# POWER.net
KiCad netlist of a schematic drawn in Altium Designer
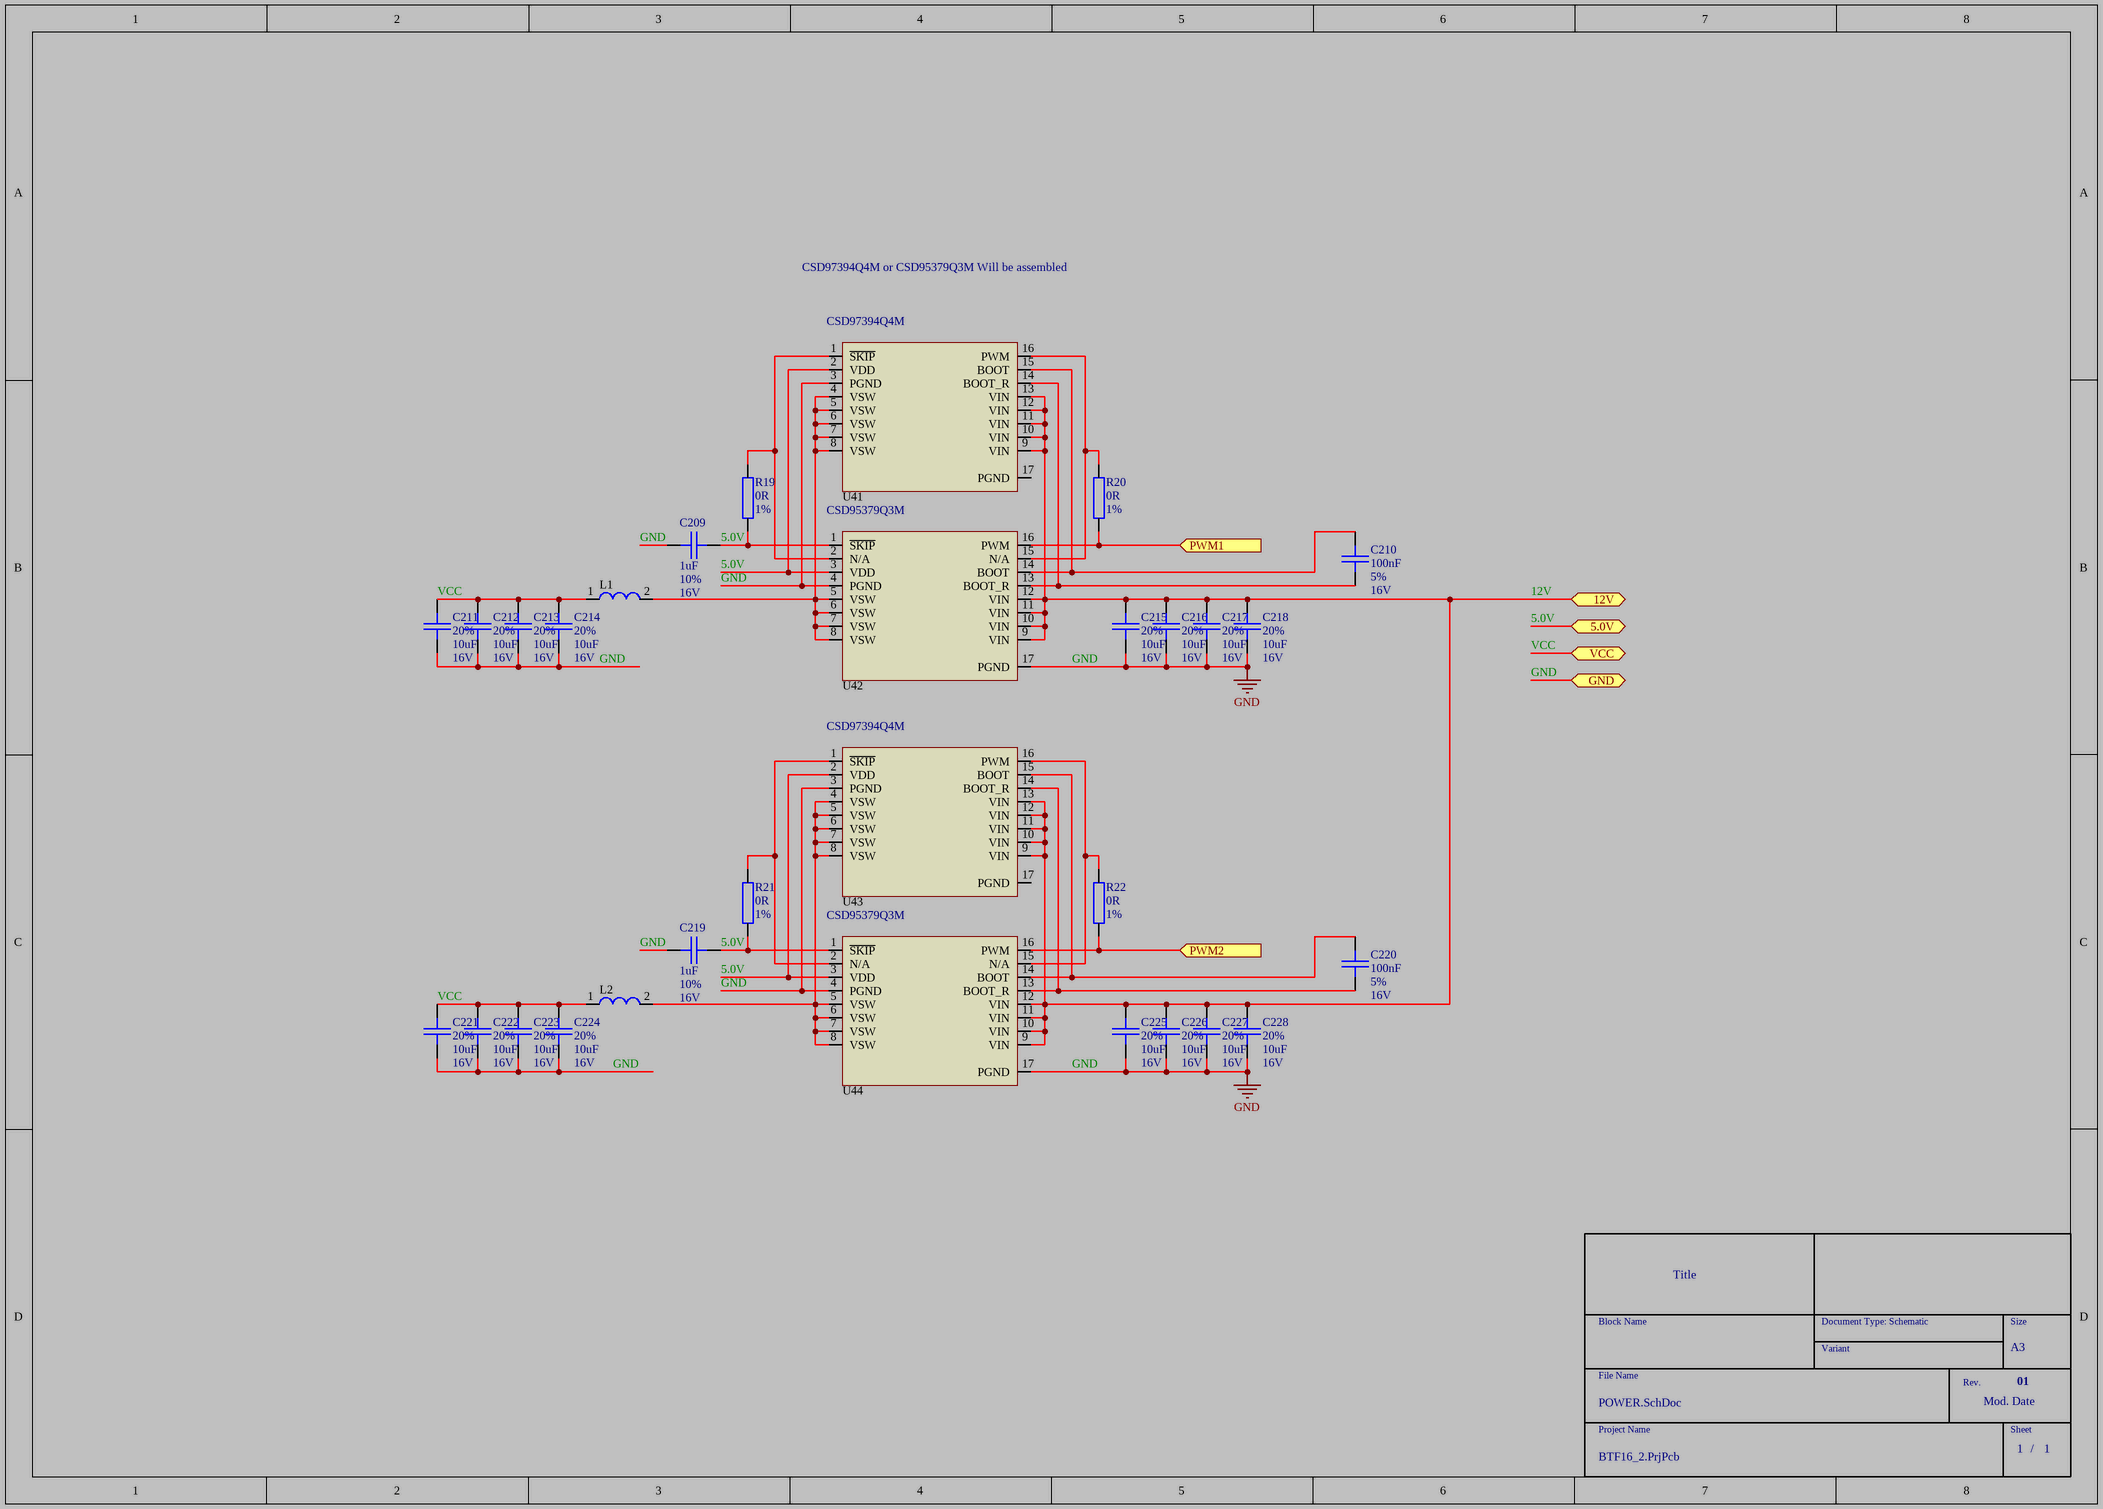
[diagram p0: POWER.SchDoc]

(export (version "E")
  (design (tool "Eeschema 10.0.6"))
  (components
    (comp (ref "C209")
      (value "C")
      (footprint "SMD_0603_CAPC1608X95N")
      (fields
        (field (name "DB_PART_NUMBER") "CAP000023307")
        (field (name "DB_VALUE") "1uF")
        (field (name "DB_TOLERANCE") "10%")
        (field (name "DB_VOLTAGE") "16V")
        (field (name "DB_MANUFACTURER_PART") "KEMET    C0603F105K4RAC")
      )
      (libsource (lib "Database_Libs1") (part "C"))
    )
    (comp (ref "C210")
      (value "C")
      (footprint "SMD_0603_CAPC1608X95N")
      (fields
        (field (name "DB_PART_NUMBER") "CAP000027134")
        (field (name "DB_VALUE") "100nF")
        (field (name "DB_TOLERANCE") "5%")
        (field (name "DB_VOLTAGE") "16V")
        (field (name "DB_MANUFACTURER_PART") "KEMET    C0603C104J4RAC")
      )
      (libsource (lib "Database_Libs1") (part "C"))
    )
    (comp (ref "C211")
      (value "C")
      (footprint "SMD_0805_CAPC2012X145N")
      (fields
        (field (name "DB_MANUFACTURER_PART") "KEMET    C0805C106M4PAC")
        (field (name "DB_PART_NUMBER") "CAP000043650")
        (field (name "DB_TOLERANCE") "20%")
        (field (name "DB_VALUE") "10uF")
        (field (name "DB_VOLTAGE") "16V")
      )
      (libsource (lib "Database_Libs1") (part "C"))
    )
    (comp (ref "C212")
      (value "C")
      (footprint "SMD_0805_CAPC2012X145N")
      (fields
        (field (name "DB_MANUFACTURER_PART") "KEMET    C0805C106M4PAC")
        (field (name "DB_PART_NUMBER") "CAP000043650")
        (field (name "DB_TOLERANCE") "20%")
        (field (name "DB_VALUE") "10uF")
        (field (name "DB_VOLTAGE") "16V")
      )
      (libsource (lib "Database_Libs1") (part "C"))
    )
    (comp (ref "C213")
      (value "C")
      (footprint "SMD_0805_CAPC2012X145N")
      (fields
        (field (name "DB_MANUFACTURER_PART") "KEMET    C0805C106M4PAC")
        (field (name "DB_PART_NUMBER") "CAP000043650")
        (field (name "DB_TOLERANCE") "20%")
        (field (name "DB_VALUE") "10uF")
        (field (name "DB_VOLTAGE") "16V")
      )
      (libsource (lib "Database_Libs1") (part "C"))
    )
    (comp (ref "C214")
      (value "C")
      (footprint "SMD_0805_CAPC2012X145N")
      (fields
        (field (name "DB_MANUFACTURER_PART") "KEMET    C0805C106M4PAC")
        (field (name "DB_PART_NUMBER") "CAP000043650")
        (field (name "DB_TOLERANCE") "20%")
        (field (name "DB_VALUE") "10uF")
        (field (name "DB_VOLTAGE") "16V")
      )
      (libsource (lib "Database_Libs1") (part "C"))
    )
    (comp (ref "C215")
      (value "C")
      (footprint "SMD_0805_CAPC2012X145N")
      (fields
        (field (name "DB_MANUFACTURER_PART") "KEMET    C0805C106M4PAC")
        (field (name "DB_PART_NUMBER") "CAP000043650")
        (field (name "DB_TOLERANCE") "20%")
        (field (name "DB_VALUE") "10uF")
        (field (name "DB_VOLTAGE") "16V")
      )
      (libsource (lib "Database_Libs1") (part "C"))
    )
    (comp (ref "C216")
      (value "C")
      (footprint "SMD_0805_CAPC2012X145N")
      (fields
        (field (name "DB_MANUFACTURER_PART") "KEMET    C0805C106M4PAC")
        (field (name "DB_PART_NUMBER") "CAP000043650")
        (field (name "DB_TOLERANCE") "20%")
        (field (name "DB_VALUE") "10uF")
        (field (name "DB_VOLTAGE") "16V")
      )
      (libsource (lib "Database_Libs1") (part "C"))
    )
    (comp (ref "C217")
      (value "C")
      (footprint "SMD_0805_CAPC2012X145N")
      (fields
        (field (name "DB_MANUFACTURER_PART") "KEMET    C0805C106M4PAC")
        (field (name "DB_PART_NUMBER") "CAP000043650")
        (field (name "DB_TOLERANCE") "20%")
        (field (name "DB_VALUE") "10uF")
        (field (name "DB_VOLTAGE") "16V")
      )
      (libsource (lib "Database_Libs1") (part "C"))
    )
    (comp (ref "C218")
      (value "C")
      (footprint "SMD_0805_CAPC2012X145N")
      (fields
        (field (name "DB_MANUFACTURER_PART") "KEMET    C0805C106M4PAC")
        (field (name "DB_PART_NUMBER") "CAP000043650")
        (field (name "DB_TOLERANCE") "20%")
        (field (name "DB_VALUE") "10uF")
        (field (name "DB_VOLTAGE") "16V")
      )
      (libsource (lib "Database_Libs1") (part "C"))
    )
    (comp (ref "C219")
      (value "C")
      (footprint "SMD_0603_CAPC1608X95N")
      (fields
        (field (name "DB_PART_NUMBER") "CAP000023307")
        (field (name "DB_VALUE") "1uF")
        (field (name "DB_TOLERANCE") "10%")
        (field (name "DB_VOLTAGE") "16V")
        (field (name "DB_MANUFACTURER_PART") "KEMET    C0603F105K4RAC")
      )
      (libsource (lib "Database_Libs1") (part "C"))
    )
    (comp (ref "C220")
      (value "C")
      (footprint "SMD_0603_CAPC1608X95N")
      (fields
        (field (name "DB_PART_NUMBER") "CAP000027134")
        (field (name "DB_VALUE") "100nF")
        (field (name "DB_TOLERANCE") "5%")
        (field (name "DB_VOLTAGE") "16V")
        (field (name "DB_MANUFACTURER_PART") "KEMET    C0603C104J4RAC")
      )
      (libsource (lib "Database_Libs1") (part "C"))
    )
    (comp (ref "C221")
      (value "C")
      (footprint "SMD_0805_CAPC2012X145N")
      (fields
        (field (name "DB_MANUFACTURER_PART") "KEMET    C0805C106M4PAC")
        (field (name "DB_PART_NUMBER") "CAP000043650")
        (field (name "DB_TOLERANCE") "20%")
        (field (name "DB_VALUE") "10uF")
        (field (name "DB_VOLTAGE") "16V")
      )
      (libsource (lib "Database_Libs1") (part "C"))
    )
    (comp (ref "C222")
      (value "C")
      (footprint "SMD_0805_CAPC2012X145N")
      (fields
        (field (name "DB_MANUFACTURER_PART") "KEMET    C0805C106M4PAC")
        (field (name "DB_PART_NUMBER") "CAP000043650")
        (field (name "DB_TOLERANCE") "20%")
        (field (name "DB_VALUE") "10uF")
        (field (name "DB_VOLTAGE") "16V")
      )
      (libsource (lib "Database_Libs1") (part "C"))
    )
    (comp (ref "C223")
      (value "C")
      (footprint "SMD_0805_CAPC2012X145N")
      (fields
        (field (name "DB_MANUFACTURER_PART") "KEMET    C0805C106M4PAC")
        (field (name "DB_PART_NUMBER") "CAP000043650")
        (field (name "DB_TOLERANCE") "20%")
        (field (name "DB_VALUE") "10uF")
        (field (name "DB_VOLTAGE") "16V")
      )
      (libsource (lib "Database_Libs1") (part "C"))
    )
    (comp (ref "C224")
      (value "C")
      (footprint "SMD_0805_CAPC2012X145N")
      (fields
        (field (name "DB_MANUFACTURER_PART") "KEMET    C0805C106M4PAC")
        (field (name "DB_PART_NUMBER") "CAP000043650")
        (field (name "DB_TOLERANCE") "20%")
        (field (name "DB_VALUE") "10uF")
        (field (name "DB_VOLTAGE") "16V")
      )
      (libsource (lib "Database_Libs1") (part "C"))
    )
    (comp (ref "C225")
      (value "C")
      (footprint "SMD_0805_CAPC2012X145N")
      (fields
        (field (name "DB_MANUFACTURER_PART") "KEMET    C0805C106M4PAC")
        (field (name "DB_PART_NUMBER") "CAP000043650")
        (field (name "DB_TOLERANCE") "20%")
        (field (name "DB_VALUE") "10uF")
        (field (name "DB_VOLTAGE") "16V")
      )
      (libsource (lib "Database_Libs1") (part "C"))
    )
    (comp (ref "C226")
      (value "C")
      (footprint "SMD_0805_CAPC2012X145N")
      (fields
        (field (name "DB_MANUFACTURER_PART") "KEMET    C0805C106M4PAC")
        (field (name "DB_PART_NUMBER") "CAP000043650")
        (field (name "DB_TOLERANCE") "20%")
        (field (name "DB_VALUE") "10uF")
        (field (name "DB_VOLTAGE") "16V")
      )
      (libsource (lib "Database_Libs1") (part "C"))
    )
    (comp (ref "C227")
      (value "C")
      (footprint "SMD_0805_CAPC2012X145N")
      (fields
        (field (name "DB_MANUFACTURER_PART") "KEMET    C0805C106M4PAC")
        (field (name "DB_PART_NUMBER") "CAP000043650")
        (field (name "DB_TOLERANCE") "20%")
        (field (name "DB_VALUE") "10uF")
        (field (name "DB_VOLTAGE") "16V")
      )
      (libsource (lib "Database_Libs1") (part "C"))
    )
    (comp (ref "C228")
      (value "C")
      (footprint "SMD_0805_CAPC2012X145N")
      (fields
        (field (name "DB_MANUFACTURER_PART") "KEMET    C0805C106M4PAC")
        (field (name "DB_PART_NUMBER") "CAP000043650")
        (field (name "DB_TOLERANCE") "20%")
        (field (name "DB_VALUE") "10uF")
        (field (name "DB_VOLTAGE") "16V")
      )
      (libsource (lib "Database_Libs1") (part "C"))
    )
    (comp (ref "L1") (value "470nH") (footprint "SMD_INDM720X665X300") (libsource (lib "DLV") (part "L")))
    (comp (ref "L2") (value "470nH") (footprint "SMD_INDM720X665X300") (libsource (lib "DLV") (part "L")))
    (comp (ref "R19")
      (value "R")
      (footprint "SMD_0603_RESC1608X55N")
      (fields
        (field (name "DB_PART_NUMBER") "RES000008926")
        (field (name "DB_VALUE") "0R")
        (field (name "DB_TOLERANCE") "1%")
        (field (name "DB_MANUFACTURER_PART") "YAGEO    AC0603FR-070RL")
        (field (name "DB_APPROVED_BY") "VSN")
      )
      (libsource (lib "Database_Libs1") (part "R"))
    )
    (comp (ref "R20")
      (value "R")
      (footprint "SMD_0603_RESC1608X55N")
      (fields
        (field (name "DB_PART_NUMBER") "RES000008926")
        (field (name "DB_VALUE") "0R")
        (field (name "DB_TOLERANCE") "1%")
        (field (name "DB_MANUFACTURER_PART") "YAGEO    AC0603FR-070RL")
        (field (name "DB_APPROVED_BY") "VSN")
      )
      (libsource (lib "Database_Libs1") (part "R"))
    )
    (comp (ref "R21")
      (value "R")
      (footprint "SMD_0603_RESC1608X55N")
      (fields
        (field (name "DB_PART_NUMBER") "RES000008926")
        (field (name "DB_VALUE") "0R")
        (field (name "DB_TOLERANCE") "1%")
        (field (name "DB_MANUFACTURER_PART") "YAGEO    AC0603FR-070RL")
        (field (name "DB_APPROVED_BY") "VSN")
      )
      (libsource (lib "Database_Libs1") (part "R"))
    )
    (comp (ref "R22")
      (value "R")
      (footprint "SMD_0603_RESC1608X55N")
      (fields
        (field (name "DB_PART_NUMBER") "RES000008926")
        (field (name "DB_VALUE") "0R")
        (field (name "DB_TOLERANCE") "1%")
        (field (name "DB_MANUFACTURER_PART") "YAGEO    AC0603FR-070RL")
        (field (name "DB_APPROVED_BY") "VSN")
      )
      (libsource (lib "Database_Libs1") (part "R"))
    )
    (comp (ref "U41")
      (value "CSD95379Q3M")
      (footprint "SMD_SON40P330X330X100-17N")
      (description "Texas Instrumendts Buck Boost DC-DC")
      (fields
        (field (name "DB_MANUFACTURER_PART") "TEXAS INSTRUMENTS  CSD97394Q4M")
        (field (name "DB_VALUE") "CSD97394Q4M")
      )
      (libsource (lib "BitCoin") (part "IC_CSD97394Q4M"))
    )
    (comp (ref "U42")
      (value "CSD95379Q3M")
      (footprint "SMD_SON40P330X330X100-17N")
      (description "Texas Instrumendts Buck Boost DC-DC")
      (fields
        (field (name "DB_MANUFACTURER_PART") "TEXAS INSTRUMENTS  CSD95379Q3M")
        (field (name "DB_VALUE") "CSD95379Q3M")
      )
      (libsource (lib "BitCoin") (part "IC_CSD95379Q3M"))
    )
    (comp (ref "U43")
      (value "CSD95379Q3M")
      (footprint "SMD_SON40P330X330X100-17N")
      (description "Texas Instrumendts Buck Boost DC-DC")
      (fields
        (field (name "DB_MANUFACTURER_PART") "TEXAS INSTRUMENTS  CSD97394Q4M")
        (field (name "DB_VALUE") "CSD97394Q4M")
      )
      (libsource (lib "BitCoin") (part "IC_CSD97394Q4M"))
    )
    (comp (ref "U44")
      (value "CSD95379Q3M")
      (footprint "SMD_SON40P330X330X100-17N")
      (description "Texas Instrumendts Buck Boost DC-DC")
      (fields
        (field (name "DB_MANUFACTURER_PART") "TEXAS INSTRUMENTS  CSD95379Q3M")
        (field (name "DB_VALUE") "CSD95379Q3M")
      )
      (libsource (lib "BitCoin") (part "IC_CSD95379Q3M"))
    )
  )
  (nets
    (net (code "1") (name "/5.0V") (class "Default")
      (node (ref "C209") (pin "1") (pinfunction "1_1") (pintype "passive"))
      (node (ref "C219") (pin "1") (pinfunction "1_1") (pintype "passive"))
      (node (ref "R19") (pin "1") (pinfunction "1_1") (pintype "passive"))
      (node (ref "R21") (pin "1") (pinfunction "1_1") (pintype "passive"))
      (node (ref "U41") (pin "2") (pinfunction "VDD_2") (pintype "passive"))
      (node (ref "U42") (pin "1") (pinfunction "~{SKIP}_1") (pintype "passive"))
      (node (ref "U42") (pin "3") (pinfunction "VDD_3") (pintype "passive"))
      (node (ref "U43") (pin "2") (pinfunction "VDD_2") (pintype "passive"))
      (node (ref "U44") (pin "1") (pinfunction "~{SKIP}_1") (pintype "passive"))
      (node (ref "U44") (pin "3") (pinfunction "VDD_3") (pintype "passive"))
    )
    (net (code "2") (name "/12V") (class "Default")
      (node (ref "C215") (pin "1") (pinfunction "1_1") (pintype "passive"))
      (node (ref "C216") (pin "1") (pinfunction "1_1") (pintype "passive"))
      (node (ref "C217") (pin "1") (pinfunction "1_1") (pintype "passive"))
      (node (ref "C218") (pin "1") (pinfunction "1_1") (pintype "passive"))
      (node (ref "C225") (pin "1") (pinfunction "1_1") (pintype "passive"))
      (node (ref "C226") (pin "1") (pinfunction "1_1") (pintype "passive"))
      (node (ref "C227") (pin "1") (pinfunction "1_1") (pintype "passive"))
      (node (ref "C228") (pin "1") (pinfunction "1_1") (pintype "passive"))
      (node (ref "U41") (pin "10") (pinfunction "VIN_10") (pintype "passive"))
      (node (ref "U41") (pin "11") (pinfunction "VIN_11") (pintype "passive"))
      (node (ref "U41") (pin "12") (pinfunction "VIN_12") (pintype "passive"))
      (node (ref "U41") (pin "13") (pinfunction "VIN_13") (pintype "passive"))
      (node (ref "U41") (pin "9") (pinfunction "VIN_9") (pintype "passive"))
      (node (ref "U42") (pin "10") (pinfunction "VIN_10") (pintype "passive"))
      (node (ref "U42") (pin "11") (pinfunction "VIN_11") (pintype "passive"))
      (node (ref "U42") (pin "12") (pinfunction "VIN_12") (pintype "passive"))
      (node (ref "U42") (pin "9") (pinfunction "VIN_9") (pintype "passive"))
      (node (ref "U43") (pin "10") (pinfunction "VIN_10") (pintype "passive"))
      (node (ref "U43") (pin "11") (pinfunction "VIN_11") (pintype "passive"))
      (node (ref "U43") (pin "12") (pinfunction "VIN_12") (pintype "passive"))
      (node (ref "U43") (pin "13") (pinfunction "VIN_13") (pintype "passive"))
      (node (ref "U43") (pin "9") (pinfunction "VIN_9") (pintype "passive"))
      (node (ref "U44") (pin "10") (pinfunction "VIN_10") (pintype "passive"))
      (node (ref "U44") (pin "11") (pinfunction "VIN_11") (pintype "passive"))
      (node (ref "U44") (pin "12") (pinfunction "VIN_12") (pintype "passive"))
      (node (ref "U44") (pin "9") (pinfunction "VIN_9") (pintype "passive"))
    )
    (net (code "3") (name "/PWM1") (class "Default")
      (node (ref "R20") (pin "1") (pinfunction "1_1") (pintype "passive"))
      (node (ref "U42") (pin "16") (pinfunction "PWM_16") (pintype "passive"))
    )
    (net (code "4") (name "/PWM2") (class "Default")
      (node (ref "R22") (pin "1") (pinfunction "1_1") (pintype "passive"))
      (node (ref "U44") (pin "16") (pinfunction "PWM_16") (pintype "passive"))
    )
    (net (code "5") (name "/VCC") (class "Default")
      (node (ref "C211") (pin "1") (pinfunction "1_1") (pintype "passive"))
      (node (ref "C212") (pin "1") (pinfunction "1_1") (pintype "passive"))
      (node (ref "C213") (pin "1") (pinfunction "1_1") (pintype "passive"))
      (node (ref "C214") (pin "1") (pinfunction "1_1") (pintype "passive"))
      (node (ref "C221") (pin "1") (pinfunction "1_1") (pintype "passive"))
      (node (ref "C222") (pin "1") (pinfunction "1_1") (pintype "passive"))
      (node (ref "C223") (pin "1") (pinfunction "1_1") (pintype "passive"))
      (node (ref "C224") (pin "1") (pinfunction "1_1") (pintype "passive"))
      (node (ref "L1") (pin "1") (pinfunction "1_1") (pintype "passive"))
      (node (ref "L2") (pin "1") (pinfunction "1_1") (pintype "passive"))
    )
    (net (code "6") (name "GND") (class "Default")
      (node (ref "C209") (pin "2") (pinfunction "2_2") (pintype "passive"))
      (node (ref "C211") (pin "2") (pinfunction "2_2") (pintype "passive"))
      (node (ref "C212") (pin "2") (pinfunction "2_2") (pintype "passive"))
      (node (ref "C213") (pin "2") (pinfunction "2_2") (pintype "passive"))
      (node (ref "C214") (pin "2") (pinfunction "2_2") (pintype "passive"))
      (node (ref "C215") (pin "2") (pinfunction "2_2") (pintype "passive"))
      (node (ref "C216") (pin "2") (pinfunction "2_2") (pintype "passive"))
      (node (ref "C217") (pin "2") (pinfunction "2_2") (pintype "passive"))
      (node (ref "C218") (pin "2") (pinfunction "2_2") (pintype "passive"))
      (node (ref "C219") (pin "2") (pinfunction "2_2") (pintype "passive"))
      (node (ref "C221") (pin "2") (pinfunction "2_2") (pintype "passive"))
      (node (ref "C222") (pin "2") (pinfunction "2_2") (pintype "passive"))
      (node (ref "C223") (pin "2") (pinfunction "2_2") (pintype "passive"))
      (node (ref "C224") (pin "2") (pinfunction "2_2") (pintype "passive"))
      (node (ref "C225") (pin "2") (pinfunction "2_2") (pintype "passive"))
      (node (ref "C226") (pin "2") (pinfunction "2_2") (pintype "passive"))
      (node (ref "C227") (pin "2") (pinfunction "2_2") (pintype "passive"))
      (node (ref "C228") (pin "2") (pinfunction "2_2") (pintype "passive"))
      (node (ref "U41") (pin "3") (pinfunction "PGND_3") (pintype "passive"))
      (node (ref "U42") (pin "17") (pinfunction "PGND_17") (pintype "passive"))
      (node (ref "U42") (pin "4") (pinfunction "PGND_4") (pintype "passive"))
      (node (ref "U43") (pin "3") (pinfunction "PGND_3") (pintype "passive"))
      (node (ref "U44") (pin "17") (pinfunction "PGND_17") (pintype "passive"))
      (node (ref "U44") (pin "4") (pinfunction "PGND_4") (pintype "passive"))
    )
    (net (code "7") (name "Net-(L1-Pad2)") (class "Default")
      (node (ref "L1") (pin "2") (pinfunction "2_2") (pintype "passive"))
      (node (ref "U41") (pin "4") (pinfunction "VSW_4") (pintype "passive"))
      (node (ref "U41") (pin "5") (pinfunction "VSW_5") (pintype "passive"))
      (node (ref "U41") (pin "6") (pinfunction "VSW_6") (pintype "passive"))
      (node (ref "U41") (pin "7") (pinfunction "VSW_7") (pintype "passive"))
      (node (ref "U41") (pin "8") (pinfunction "VSW_8") (pintype "passive"))
      (node (ref "U42") (pin "5") (pinfunction "VSW_5") (pintype "passive"))
      (node (ref "U42") (pin "6") (pinfunction "VSW_6") (pintype "passive"))
      (node (ref "U42") (pin "7") (pinfunction "VSW_7") (pintype "passive"))
      (node (ref "U42") (pin "8") (pinfunction "VSW_8") (pintype "passive"))
    )
    (net (code "8") (name "Net-(L2-Pad2)") (class "Default")
      (node (ref "L2") (pin "2") (pinfunction "2_2") (pintype "passive"))
      (node (ref "U43") (pin "4") (pinfunction "VSW_4") (pintype "passive"))
      (node (ref "U43") (pin "5") (pinfunction "VSW_5") (pintype "passive"))
      (node (ref "U43") (pin "6") (pinfunction "VSW_6") (pintype "passive"))
      (node (ref "U43") (pin "7") (pinfunction "VSW_7") (pintype "passive"))
      (node (ref "U43") (pin "8") (pinfunction "VSW_8") (pintype "passive"))
      (node (ref "U44") (pin "5") (pinfunction "VSW_5") (pintype "passive"))
      (node (ref "U44") (pin "6") (pinfunction "VSW_6") (pintype "passive"))
      (node (ref "U44") (pin "7") (pinfunction "VSW_7") (pintype "passive"))
      (node (ref "U44") (pin "8") (pinfunction "VSW_8") (pintype "passive"))
    )
    (net (code "9") (name "Net-(U41-BOOT)") (class "Default")
      (node (ref "C210") (pin "1") (pinfunction "1_1") (pintype "passive"))
      (node (ref "U41") (pin "15") (pinfunction "BOOT_15") (pintype "passive"))
      (node (ref "U42") (pin "14") (pinfunction "BOOT_14") (pintype "passive"))
    )
    (net (code "10") (name "Net-(U41-BOOT_R)") (class "Default")
      (node (ref "C210") (pin "2") (pinfunction "2_2") (pintype "passive"))
      (node (ref "U41") (pin "14") (pinfunction "BOOT_R_14") (pintype "passive"))
      (node (ref "U42") (pin "13") (pinfunction "BOOT_R_13") (pintype "passive"))
    )
    (net (code "11") (name "Net-(U41-PWM)") (class "Default")
      (node (ref "R20") (pin "2") (pinfunction "2_2") (pintype "passive"))
      (node (ref "U41") (pin "16") (pinfunction "PWM_16") (pintype "passive"))
      (node (ref "U42") (pin "15") (pinfunction "N/A_15") (pintype "passive"))
    )
    (net (code "12") (name "Net-(U41-~{SKIP})") (class "Default")
      (node (ref "R19") (pin "2") (pinfunction "2_2") (pintype "passive"))
      (node (ref "U41") (pin "1") (pinfunction "~{SKIP}_1") (pintype "passive"))
      (node (ref "U42") (pin "2") (pinfunction "N/A_2") (pintype "passive"))
    )
    (net (code "13") (name "Net-(U43-BOOT)") (class "Default")
      (node (ref "C220") (pin "1") (pinfunction "1_1") (pintype "passive"))
      (node (ref "U43") (pin "15") (pinfunction "BOOT_15") (pintype "passive"))
      (node (ref "U44") (pin "14") (pinfunction "BOOT_14") (pintype "passive"))
    )
    (net (code "14") (name "Net-(U43-BOOT_R)") (class "Default")
      (node (ref "C220") (pin "2") (pinfunction "2_2") (pintype "passive"))
      (node (ref "U43") (pin "14") (pinfunction "BOOT_R_14") (pintype "passive"))
      (node (ref "U44") (pin "13") (pinfunction "BOOT_R_13") (pintype "passive"))
    )
    (net (code "15") (name "Net-(U43-PWM)") (class "Default")
      (node (ref "R22") (pin "2") (pinfunction "2_2") (pintype "passive"))
      (node (ref "U43") (pin "16") (pinfunction "PWM_16") (pintype "passive"))
      (node (ref "U44") (pin "15") (pinfunction "N/A_15") (pintype "passive"))
    )
    (net (code "16") (name "Net-(U43-~{SKIP})") (class "Default")
      (node (ref "R21") (pin "2") (pinfunction "2_2") (pintype "passive"))
      (node (ref "U43") (pin "1") (pinfunction "~{SKIP}_1") (pintype "passive"))
      (node (ref "U44") (pin "2") (pinfunction "N/A_2") (pintype "passive"))
    )
    (net (code "17") (name "unconnected-(U41-PGND-Pad17)") (class "Default")
      (node (ref "U41") (pin "17") (pinfunction "PGND_17") (pintype "passive"))
    )
    (net (code "18") (name "unconnected-(U43-PGND-Pad17)") (class "Default")
      (node (ref "U43") (pin "17") (pinfunction "PGND_17") (pintype "passive"))
    )
  )
)
